# Mainboard_MCU_Func.net
KiCad netlist of a schematic drawn in Altium Designer
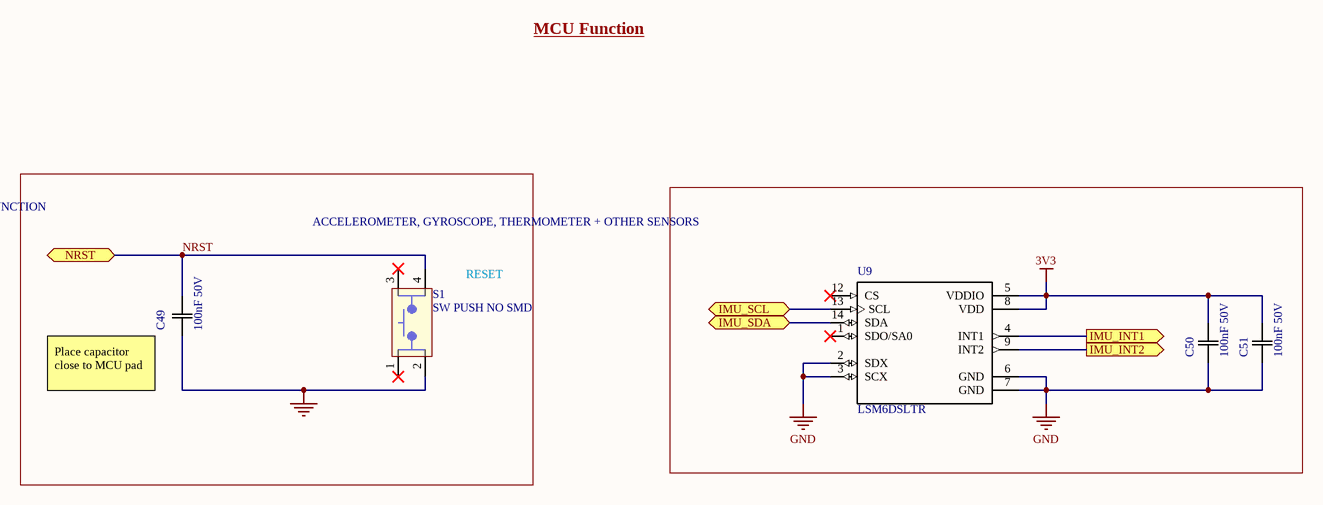
[diagram p0: Mainboard_MCU_Func.SchDoc]

(export (version "E")
  (design (tool "Eeschema 10.0.6"))
  (components
    (comp (ref "C49")
      (value "100nF 50V")
      (footprint "0603")
      (description "CAP CER 0.1UF 50V X7R 0805")
      (fields (field (name "TOLERANCE") "10%"))
      (libsource (lib "AltiumLibraries") (part "CAP 100nF 50V"))
    )
    (comp (ref "C50")
      (value "100nF 50V")
      (footprint "0603")
      (description "CAP CER 0.1UF 50V X7R 0805")
      (fields (field (name "TOLERANCE") "10%"))
      (libsource (lib "AltiumLibraries") (part "CAP 100nF 50V"))
    )
    (comp (ref "C51")
      (value "100nF 50V")
      (footprint "0603")
      (description "CAP CER 0.1UF 50V X7R 0805")
      (fields (field (name "TOLERANCE") "10%"))
      (libsource (lib "AltiumLibraries") (part "CAP 100nF 50V"))
    )
    (comp (ref "S1")
      (value "SW PUSH NO SMD")
      (footprint "TL3305")
      (description "Tactile Switch SPST-NO Top Actuated Surface Mount 12V 50mA")
      (fields (field (name "MF") "E-Switch") (field (name "MP") "TL3305BF260QG"))
      (libsource (lib "AltiumLibraries") (part "SW PUSH NO SMD"))
    )
    (comp (ref "U9")
      (value "LSM6DSLTR")
      (footprint "LGA-14")
      (description "IMU ACCEL/GYRO I2C/SPI 14LGA")
      (fields (field (name "MF") "STMicroelectronics"))
      (libsource (lib "AltiumLibraries") (part "IMU LSM6DSLTR"))
    )
  )
  (nets
    (net (code "1") (name "/IMU_INT1") (class "Default")
      (node (ref "U9") (pin "4") (pinfunction "INT1_4") (pintype "output"))
    )
    (net (code "2") (name "/IMU_INT2") (class "Default")
      (node (ref "U9") (pin "9") (pinfunction "INT2_9") (pintype "output"))
    )
    (net (code "3") (name "/IMU_SCL") (class "Default")
      (node (ref "U9") (pin "13") (pinfunction "SCL_13") (pintype "input"))
    )
    (net (code "4") (name "/IMU_SDA") (class "Default")
      (node (ref "U9") (pin "14") (pinfunction "SDA_14") (pintype "bidirectional"))
    )
    (net (code "5") (name "/NRST") (class "Default")
      (node (ref "C49") (pin "2") (pinfunction "C2_2") (pintype "passive"))
      (node (ref "S1") (pin "4") (pinfunction "4_4") (pintype "passive"))
    )
    (net (code "6") (name "3V3") (class "Default")
      (node (ref "C50") (pin "2") (pinfunction "C2_2") (pintype "passive"))
      (node (ref "C51") (pin "2") (pinfunction "C2_2") (pintype "passive"))
      (node (ref "U9") (pin "5") (pinfunction "VDDIO_5") (pintype "power_in"))
      (node (ref "U9") (pin "8") (pinfunction "VDD_8") (pintype "power_in"))
    )
    (net (code "7") (name "GND") (class "Default")
      (node (ref "C49") (pin "1") (pinfunction "C1_1") (pintype "passive"))
      (node (ref "C50") (pin "1") (pinfunction "C1_1") (pintype "passive"))
      (node (ref "C51") (pin "1") (pinfunction "C1_1") (pintype "passive"))
      (node (ref "S1") (pin "2") (pinfunction "2_2") (pintype "passive"))
      (node (ref "U9") (pin "2") (pinfunction "SDX_2") (pintype "bidirectional"))
      (node (ref "U9") (pin "3") (pinfunction "SCX_3") (pintype "bidirectional"))
      (node (ref "U9") (pin "6") (pinfunction "GND_6") (pintype "power_in"))
      (node (ref "U9") (pin "7") (pinfunction "GND_7") (pintype "power_in"))
    )
    (net (code "8") (name "unconnected-(S1-Pad1)") (class "Default")
      (node (ref "S1") (pin "1") (pinfunction "1_1") (pintype "passive+no_connect"))
    )
    (net (code "9") (name "unconnected-(S1-Pad3)") (class "Default")
      (node (ref "S1") (pin "3") (pinfunction "3_3") (pintype "passive+no_connect"))
    )
    (net (code "10") (name "unconnected-(U9-CS-Pad12)") (class "Default")
      (node (ref "U9") (pin "12") (pinfunction "CS_12") (pintype "input+no_connect"))
    )
    (net (code "11") (name "unconnected-(U9-SDO{slash}SA0-Pad1)") (class "Default")
      (node (ref "U9") (pin "1") (pinfunction "SDO/SA0_1") (pintype "bidirectional+no_connect"))
    )
  )
)
